# design.net
KiCad netlist of a schematic drawn in Altium Designer
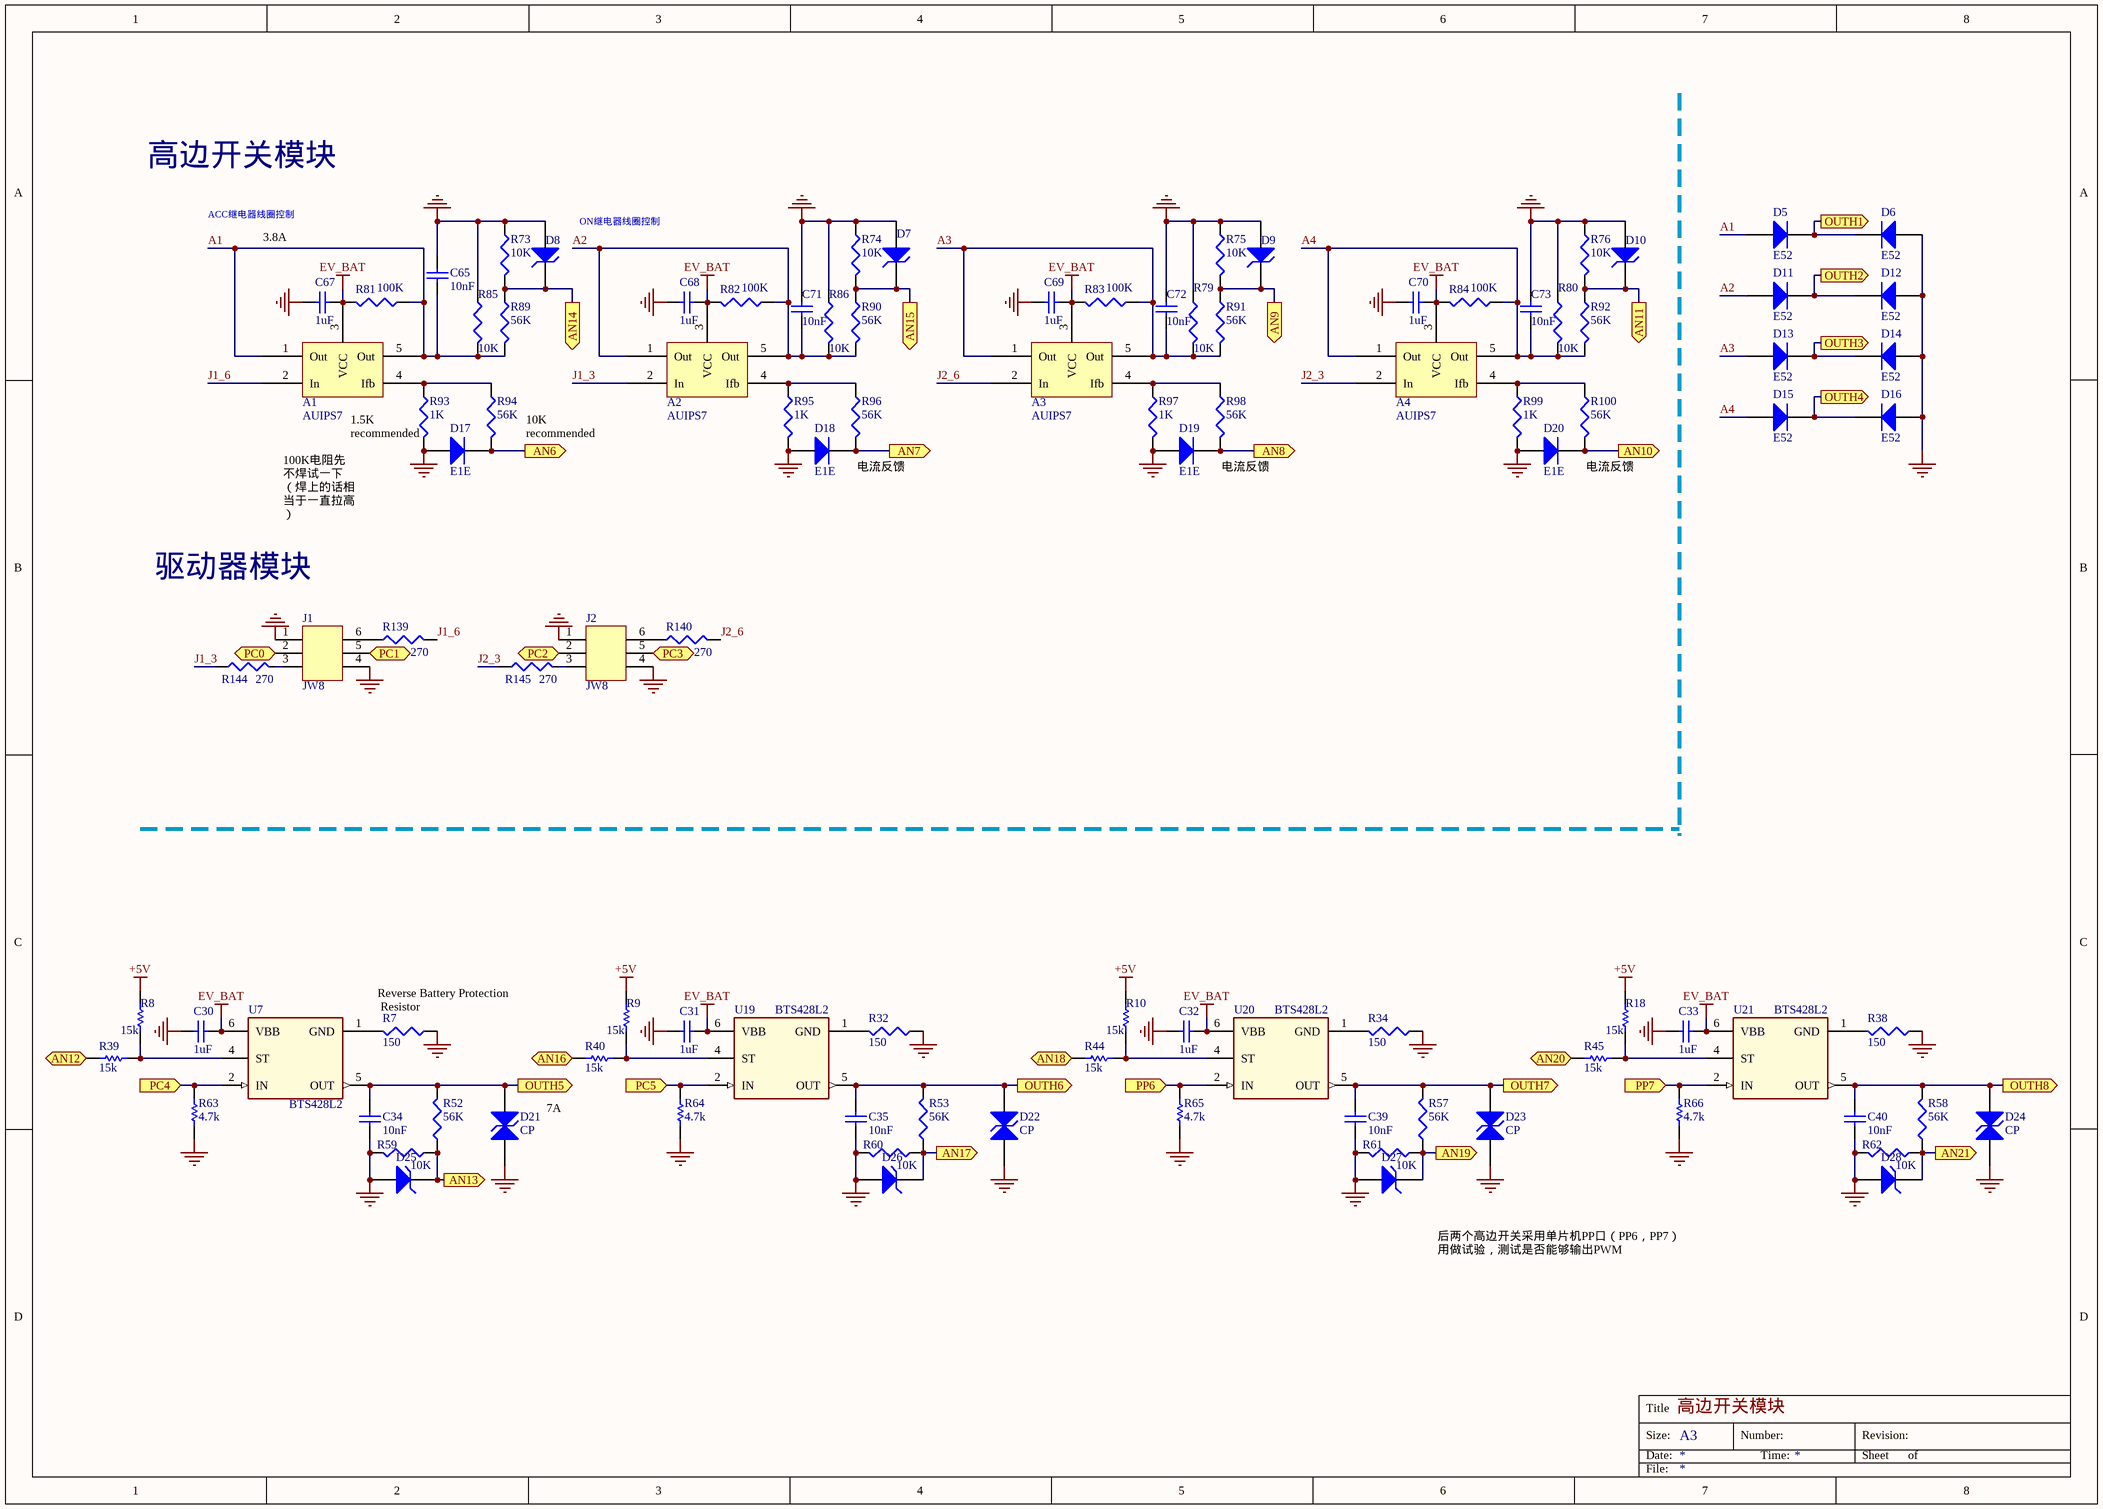
[diagram p0: 高边开关模块.SchDoc]

(export (version "E")
  (design (tool "Eeschema 10.0.6"))
  (components
    (comp (ref "A1") (value "AUIPS7") (footprint "AUIPS7") (libsource (lib "整车控制器") (part "AUIPS7")))
    (comp (ref "A2") (value "AUIPS7") (footprint "AUIPS7") (libsource (lib "整车控制器") (part "AUIPS7")))
    (comp (ref "A3") (value "AUIPS7") (footprint "AUIPS7") (libsource (lib "整车控制器") (part "AUIPS7")))
    (comp (ref "A4") (value "AUIPS7") (footprint "AUIPS7") (libsource (lib "整车控制器") (part "AUIPS7")))
    (comp (ref "C30")
      (value "1uF")
      (footprint "0603-L")
      (description "Capacitor")
      (fields (field (name "Comment") "Cap") (field (name "PUBLISHER") "Altium Limited"))
      (libsource (lib "Miscellaneous Devices") (part "Cap"))
    )
    (comp (ref "C31")
      (value "1uF")
      (footprint "0603-L")
      (description "Capacitor")
      (fields (field (name "Comment") "Cap") (field (name "PUBLISHER") "Altium Limited"))
      (libsource (lib "Miscellaneous Devices") (part "Cap"))
    )
    (comp (ref "C32")
      (value "1uF")
      (footprint "0603-L")
      (description "Capacitor")
      (fields (field (name "Comment") "Cap") (field (name "PUBLISHER") "Altium Limited"))
      (libsource (lib "Miscellaneous Devices") (part "Cap"))
    )
    (comp (ref "C33")
      (value "1uF")
      (footprint "0603-L")
      (description "Capacitor")
      (fields (field (name "Comment") "Cap") (field (name "PUBLISHER") "Altium Limited"))
      (libsource (lib "Miscellaneous Devices") (part "Cap"))
    )
    (comp (ref "C34")
      (value "10nF")
      (footprint "0603-L")
      (description "Capacitor")
      (fields (field (name "Comment") "Cap") (field (name "PUBLISHER") "Altium Limited"))
      (libsource (lib "Miscellaneous Devices") (part "Cap"))
    )
    (comp (ref "C35")
      (value "10nF")
      (footprint "0603-L")
      (description "Capacitor")
      (fields (field (name "Comment") "Cap") (field (name "PUBLISHER") "Altium Limited"))
      (libsource (lib "Miscellaneous Devices") (part "Cap"))
    )
    (comp (ref "C39")
      (value "10nF")
      (footprint "0603-L")
      (description "Capacitor")
      (fields (field (name "Comment") "Cap") (field (name "PUBLISHER") "Altium Limited"))
      (libsource (lib "Miscellaneous Devices") (part "Cap"))
    )
    (comp (ref "C40")
      (value "10nF")
      (footprint "0603-L")
      (description "Capacitor")
      (fields (field (name "Comment") "Cap") (field (name "PUBLISHER") "Altium Limited"))
      (libsource (lib "Miscellaneous Devices") (part "Cap"))
    )
    (comp (ref "C65")
      (value "10nF")
      (footprint "0603-L")
      (description "Capacitor")
      (fields (field (name "Comment") "Cap") (field (name "PUBLISHER") "Altium Limited"))
      (libsource (lib "Miscellaneous Devices") (part "Cap"))
    )
    (comp (ref "C67")
      (value "1uF")
      (footprint "0603-L")
      (description "Capacitor")
      (fields (field (name "Comment") "Cap") (field (name "PUBLISHER") "Altium Limited"))
      (libsource (lib "Miscellaneous Devices") (part "Cap"))
    )
    (comp (ref "C68")
      (value "1uF")
      (footprint "0603-L")
      (description "Capacitor")
      (fields (field (name "Comment") "Cap") (field (name "PUBLISHER") "Altium Limited"))
      (libsource (lib "Miscellaneous Devices") (part "Cap"))
    )
    (comp (ref "C69")
      (value "1uF")
      (footprint "0603-L")
      (description "Capacitor")
      (fields (field (name "Comment") "Cap") (field (name "PUBLISHER") "Altium Limited"))
      (libsource (lib "Miscellaneous Devices") (part "Cap"))
    )
    (comp (ref "C70")
      (value "1uF")
      (footprint "0603-L")
      (description "Capacitor")
      (fields (field (name "Comment") "Cap") (field (name "PUBLISHER") "Altium Limited"))
      (libsource (lib "Miscellaneous Devices") (part "Cap"))
    )
    (comp (ref "C71")
      (value "10nF")
      (footprint "0603-L")
      (description "Capacitor")
      (fields (field (name "Comment") "Cap") (field (name "PUBLISHER") "Altium Limited"))
      (libsource (lib "Miscellaneous Devices") (part "Cap"))
    )
    (comp (ref "C72")
      (value "10nF")
      (footprint "0603-L")
      (description "Capacitor")
      (fields (field (name "Comment") "Cap") (field (name "PUBLISHER") "Altium Limited"))
      (libsource (lib "Miscellaneous Devices") (part "Cap"))
    )
    (comp (ref "C73")
      (value "10nF")
      (footprint "0603-L")
      (description "Capacitor")
      (fields (field (name "Comment") "Cap") (field (name "PUBLISHER") "Altium Limited"))
      (libsource (lib "Miscellaneous Devices") (part "Cap"))
    )
    (comp (ref "D5")
      (value "E52")
      (footprint "整车控制器:E52")
      (description "Default Diode")
      (fields (field (name "PUBLISHER") "Altium Limited"))
      (libsource (lib "Miscellaneous Devices") (part "Diode"))
    )
    (comp (ref "D6")
      (value "E52")
      (footprint "整车控制器:E52")
      (description "Default Diode")
      (fields (field (name "PUBLISHER") "Altium Limited"))
      (libsource (lib "Miscellaneous Devices") (part "Diode"))
    )
    (comp (ref "D7")
      (value "D Zener")
      (footprint "0805")
      (description "Zener Diode")
      (fields (field (name "PUBLISHER") "Altium Limited"))
      (libsource (lib "Miscellaneous Devices") (part "D Zener"))
    )
    (comp (ref "D8")
      (value "D Zener")
      (footprint "0805")
      (description "Zener Diode")
      (fields (field (name "PUBLISHER") "Altium Limited"))
      (libsource (lib "Miscellaneous Devices") (part "D Zener"))
    )
    (comp (ref "D9")
      (value "D Zener")
      (footprint "0805")
      (description "Zener Diode")
      (fields (field (name "PUBLISHER") "Altium Limited"))
      (libsource (lib "Miscellaneous Devices") (part "D Zener"))
    )
    (comp (ref "D10")
      (value "D Zener")
      (footprint "0805")
      (description "Zener Diode")
      (fields (field (name "PUBLISHER") "Altium Limited"))
      (libsource (lib "Miscellaneous Devices") (part "D Zener"))
    )
    (comp (ref "D11")
      (value "E52")
      (footprint "整车控制器:E52")
      (description "Default Diode")
      (fields (field (name "PUBLISHER") "Altium Limited"))
      (libsource (lib "Miscellaneous Devices") (part "Diode"))
    )
    (comp (ref "D12")
      (value "E52")
      (footprint "整车控制器:E52")
      (description "Default Diode")
      (fields (field (name "PUBLISHER") "Altium Limited"))
      (libsource (lib "Miscellaneous Devices") (part "Diode"))
    )
    (comp (ref "D13")
      (value "E52")
      (footprint "整车控制器:E52")
      (description "Default Diode")
      (fields (field (name "PUBLISHER") "Altium Limited"))
      (libsource (lib "Miscellaneous Devices") (part "Diode"))
    )
    (comp (ref "D14")
      (value "E52")
      (footprint "整车控制器:E52")
      (description "Default Diode")
      (fields (field (name "PUBLISHER") "Altium Limited"))
      (libsource (lib "Miscellaneous Devices") (part "Diode"))
    )
    (comp (ref "D15")
      (value "E52")
      (footprint "整车控制器:E52")
      (description "Default Diode")
      (fields (field (name "PUBLISHER") "Altium Limited"))
      (libsource (lib "Miscellaneous Devices") (part "Diode"))
    )
    (comp (ref "D16")
      (value "E52")
      (footprint "整车控制器:E52")
      (description "Default Diode")
      (fields (field (name "PUBLISHER") "Altium Limited"))
      (libsource (lib "Miscellaneous Devices") (part "Diode"))
    )
    (comp (ref "D17")
      (value "E1E")
      (footprint "E1E")
      (description "Default Diode")
      (fields (field (name "PUBLISHER") "Altium Limited"))
      (libsource (lib "Miscellaneous Devices") (part "Diode"))
    )
    (comp (ref "D18")
      (value "E1E")
      (footprint "E1E")
      (description "Default Diode")
      (fields (field (name "PUBLISHER") "Altium Limited"))
      (libsource (lib "Miscellaneous Devices") (part "Diode"))
    )
    (comp (ref "D19")
      (value "E1E")
      (footprint "E1E")
      (description "Default Diode")
      (fields (field (name "PUBLISHER") "Altium Limited"))
      (libsource (lib "Miscellaneous Devices") (part "Diode"))
    )
    (comp (ref "D20")
      (value "E1E")
      (footprint "E1E")
      (description "Default Diode")
      (fields (field (name "PUBLISHER") "Altium Limited"))
      (libsource (lib "Miscellaneous Devices") (part "Diode"))
    )
    (comp (ref "D21") (value "CP") (footprint "E52") (libsource (lib "整车控制器") (part "CP")))
    (comp (ref "D22") (value "CP") (footprint "E52") (libsource (lib "整车控制器") (part "CP")))
    (comp (ref "D23") (value "CP") (footprint "E52") (libsource (lib "整车控制器") (part "CP")))
    (comp (ref "D24") (value "CP") (footprint "E52") (libsource (lib "整车控制器") (part "CP")))
    (comp (ref "D25")
      (value "D Zener")
      (footprint "0805")
      (description "Zener Diode")
      (fields (field (name "PUBLISHER") "Altium Limited"))
      (libsource (lib "Miscellaneous Devices") (part "D Zener"))
    )
    (comp (ref "D26")
      (value "D Zener")
      (footprint "0805")
      (description "Zener Diode")
      (fields (field (name "PUBLISHER") "Altium Limited"))
      (libsource (lib "Miscellaneous Devices") (part "D Zener"))
    )
    (comp (ref "D27")
      (value "D Zener")
      (footprint "0805")
      (description "Zener Diode")
      (fields (field (name "PUBLISHER") "Altium Limited"))
      (libsource (lib "Miscellaneous Devices") (part "D Zener"))
    )
    (comp (ref "D28")
      (value "D Zener")
      (footprint "0805")
      (description "Zener Diode")
      (fields (field (name "PUBLISHER") "Altium Limited"))
      (libsource (lib "Miscellaneous Devices") (part "D Zener"))
    )
    (comp (ref "J1")
      (value "JW8")
      (footprint "JW8")
      (description "inductive load driver")
      (libsource (lib "整车控制器") (part "JW8"))
    )
    (comp (ref "J2")
      (value "JW8")
      (footprint "JW8")
      (description "inductive load driver")
      (libsource (lib "整车控制器") (part "JW8"))
    )
    (comp (ref "R7")
      (value "150")
      (footprint "RES1206")
      (description "Resistor")
      (fields (field (name "Comment") "Res3") (field (name "PUBLISHER") "Altium Limited"))
      (libsource (lib "Miscellaneous Devices") (part "Res3"))
    )
    (comp (ref "R8")
      (value "15k")
      (footprint "0603-Resistor")
      (description "RES, 10k ohm, 0.1%, 0.1W, 0603")
      (fields
        (field (name "MANUFACTURER") "YAGEO")
        (field (name "PARTNUMBER") "RT0603BRD0710KL")
        (field (name "PUBLISHER") "YAGEO")
      )
      (libsource (lib "Resistor") (part "RT0603BRD0710KL"))
    )
    (comp (ref "R9")
      (value "15k")
      (footprint "0603-Resistor")
      (description "RES, 10k ohm, 0.1%, 0.1W, 0603")
      (fields
        (field (name "MANUFACTURER") "YAGEO")
        (field (name "PARTNUMBER") "RT0603BRD0710KL")
        (field (name "PUBLISHER") "YAGEO")
      )
      (libsource (lib "Resistor") (part "RT0603BRD0710KL"))
    )
    (comp (ref "R10")
      (value "15k")
      (footprint "0603-Resistor")
      (description "RES, 10k ohm, 0.1%, 0.1W, 0603")
      (fields
        (field (name "MANUFACTURER") "YAGEO")
        (field (name "PARTNUMBER") "RT0603BRD0710KL")
        (field (name "PUBLISHER") "YAGEO")
      )
      (libsource (lib "Resistor") (part "RT0603BRD0710KL"))
    )
    (comp (ref "R18")
      (value "15k")
      (footprint "0603-Resistor")
      (description "RES, 10k ohm, 0.1%, 0.1W, 0603")
      (fields
        (field (name "MANUFACTURER") "YAGEO")
        (field (name "PARTNUMBER") "RT0603BRD0710KL")
        (field (name "PUBLISHER") "YAGEO")
      )
      (libsource (lib "Resistor") (part "RT0603BRD0710KL"))
    )
    (comp (ref "R32")
      (value "150")
      (footprint "RES1206")
      (description "Resistor")
      (fields (field (name "Comment") "Res3") (field (name "PUBLISHER") "Altium Limited"))
      (libsource (lib "Miscellaneous Devices") (part "Res3"))
    )
    (comp (ref "R34")
      (value "150")
      (footprint "RES1206")
      (description "Resistor")
      (fields (field (name "Comment") "Res3") (field (name "PUBLISHER") "Altium Limited"))
      (libsource (lib "Miscellaneous Devices") (part "Res3"))
    )
    (comp (ref "R38")
      (value "150")
      (footprint "RES1206")
      (description "Resistor")
      (fields (field (name "Comment") "Res3") (field (name "PUBLISHER") "Altium Limited"))
      (libsource (lib "Miscellaneous Devices") (part "Res3"))
    )
    (comp (ref "R39")
      (value "15k")
      (footprint "0603-Resistor")
      (description "RES, 10k ohm, 0.1%, 0.1W, 0603")
      (fields
        (field (name "MANUFACTURER") "YAGEO")
        (field (name "PARTNUMBER") "RT0603BRD0710KL")
        (field (name "PUBLISHER") "YAGEO")
      )
      (libsource (lib "Resistor") (part "RT0603BRD0710KL"))
    )
    (comp (ref "R40")
      (value "15k")
      (footprint "0603-Resistor")
      (description "RES, 10k ohm, 0.1%, 0.1W, 0603")
      (fields
        (field (name "MANUFACTURER") "YAGEO")
        (field (name "PARTNUMBER") "RT0603BRD0710KL")
        (field (name "PUBLISHER") "YAGEO")
      )
      (libsource (lib "Resistor") (part "RT0603BRD0710KL"))
    )
    (comp (ref "R44")
      (value "15k")
      (footprint "0603-Resistor")
      (description "RES, 10k ohm, 0.1%, 0.1W, 0603")
      (fields
        (field (name "MANUFACTURER") "YAGEO")
        (field (name "PARTNUMBER") "RT0603BRD0710KL")
        (field (name "PUBLISHER") "YAGEO")
      )
      (libsource (lib "Resistor") (part "RT0603BRD0710KL"))
    )
    (comp (ref "R45")
      (value "15k")
      (footprint "0603-Resistor")
      (description "RES, 10k ohm, 0.1%, 0.1W, 0603")
      (fields
        (field (name "MANUFACTURER") "YAGEO")
        (field (name "PARTNUMBER") "RT0603BRD0710KL")
        (field (name "PUBLISHER") "YAGEO")
      )
      (libsource (lib "Resistor") (part "RT0603BRD0710KL"))
    )
    (comp (ref "R52")
      (value "56K")
      (footprint "0603-L")
      (description "Resistor")
      (fields (field (name "Comment") "Res3") (field (name "PUBLISHER") "Altium Limited"))
      (libsource (lib "Miscellaneous Devices") (part "Res3"))
    )
    (comp (ref "R53")
      (value "56K")
      (footprint "0603-L")
      (description "Resistor")
      (fields (field (name "Comment") "Res3") (field (name "PUBLISHER") "Altium Limited"))
      (libsource (lib "Miscellaneous Devices") (part "Res3"))
    )
    (comp (ref "R57")
      (value "56K")
      (footprint "0603-L")
      (description "Resistor")
      (fields (field (name "Comment") "Res3") (field (name "PUBLISHER") "Altium Limited"))
      (libsource (lib "Miscellaneous Devices") (part "Res3"))
    )
    (comp (ref "R58")
      (value "56K")
      (footprint "0603-L")
      (description "Resistor")
      (fields (field (name "Comment") "Res3") (field (name "PUBLISHER") "Altium Limited"))
      (libsource (lib "Miscellaneous Devices") (part "Res3"))
    )
    (comp (ref "R59")
      (value "10K")
      (footprint "0603-L")
      (description "Resistor")
      (fields (field (name "Comment") "Res3") (field (name "PUBLISHER") "Altium Limited"))
      (libsource (lib "Miscellaneous Devices") (part "Res3"))
    )
    (comp (ref "R60")
      (value "10K")
      (footprint "0603-L")
      (description "Resistor")
      (fields (field (name "Comment") "Res3") (field (name "PUBLISHER") "Altium Limited"))
      (libsource (lib "Miscellaneous Devices") (part "Res3"))
    )
    (comp (ref "R61")
      (value "10K")
      (footprint "0603-L")
      (description "Resistor")
      (fields (field (name "Comment") "Res3") (field (name "PUBLISHER") "Altium Limited"))
      (libsource (lib "Miscellaneous Devices") (part "Res3"))
    )
    (comp (ref "R62")
      (value "10K")
      (footprint "0603-L")
      (description "Resistor")
      (fields (field (name "Comment") "Res3") (field (name "PUBLISHER") "Altium Limited"))
      (libsource (lib "Miscellaneous Devices") (part "Res3"))
    )
    (comp (ref "R63")
      (value "4.7k")
      (footprint "0603-Resistor")
      (description "RES, 4.7k ohm, 1%, 0.1W, 0603")
      (fields
        (field (name "MANUFACTURER") "YAGEO")
        (field (name "PARTNUMBER") "RC0603FR-074K7L")
        (field (name "PUBLISHER") "YAGEO")
      )
      (libsource (lib "Resistor") (part "RC0603FR-074K7L"))
    )
    (comp (ref "R64")
      (value "4.7k")
      (footprint "0603-Resistor")
      (description "RES, 4.7k ohm, 1%, 0.1W, 0603")
      (fields
        (field (name "MANUFACTURER") "YAGEO")
        (field (name "PARTNUMBER") "RC0603FR-074K7L")
        (field (name "PUBLISHER") "YAGEO")
      )
      (libsource (lib "Resistor") (part "RC0603FR-074K7L"))
    )
    (comp (ref "R65")
      (value "4.7k")
      (footprint "0603-Resistor")
      (description "RES, 4.7k ohm, 1%, 0.1W, 0603")
      (fields
        (field (name "MANUFACTURER") "YAGEO")
        (field (name "PARTNUMBER") "RC0603FR-074K7L")
        (field (name "PUBLISHER") "YAGEO")
      )
      (libsource (lib "Resistor") (part "RC0603FR-074K7L"))
    )
    (comp (ref "R66")
      (value "4.7k")
      (footprint "0603-Resistor")
      (description "RES, 4.7k ohm, 1%, 0.1W, 0603")
      (fields
        (field (name "MANUFACTURER") "YAGEO")
        (field (name "PARTNUMBER") "RC0603FR-074K7L")
        (field (name "PUBLISHER") "YAGEO")
      )
      (libsource (lib "Resistor") (part "RC0603FR-074K7L"))
    )
    (comp (ref "R73")
      (value "10K")
      (footprint "0603-L")
      (description "Resistor")
      (fields (field (name "Comment") "Res3") (field (name "PUBLISHER") "Altium Limited"))
      (libsource (lib "Miscellaneous Devices") (part "Res3"))
    )
    (comp (ref "R74")
      (value "10K")
      (footprint "0603-L")
      (description "Resistor")
      (fields (field (name "Comment") "Res3") (field (name "PUBLISHER") "Altium Limited"))
      (libsource (lib "Miscellaneous Devices") (part "Res3"))
    )
    (comp (ref "R75")
      (value "10K")
      (footprint "0603-L")
      (description "Resistor")
      (fields (field (name "Comment") "Res3") (field (name "PUBLISHER") "Altium Limited"))
      (libsource (lib "Miscellaneous Devices") (part "Res3"))
    )
    (comp (ref "R76")
      (value "10K")
      (footprint "0603-L")
      (description "Resistor")
      (fields (field (name "Comment") "Res3") (field (name "PUBLISHER") "Altium Limited"))
      (libsource (lib "Miscellaneous Devices") (part "Res3"))
    )
    (comp (ref "R79")
      (value "10K")
      (footprint "0603-L")
      (description "Resistor")
      (fields (field (name "Comment") "Res3") (field (name "PUBLISHER") "Altium Limited"))
      (libsource (lib "Miscellaneous Devices") (part "Res3"))
    )
    (comp (ref "R80")
      (value "10K")
      (footprint "0603-L")
      (description "Resistor")
      (fields (field (name "Comment") "Res3") (field (name "PUBLISHER") "Altium Limited"))
      (libsource (lib "Miscellaneous Devices") (part "Res3"))
    )
    (comp (ref "R81")
      (value "100K")
      (footprint "0603-L")
      (description "Resistor")
      (fields (field (name "Comment") "Res3") (field (name "PUBLISHER") "Altium Limited"))
      (libsource (lib "Miscellaneous Devices") (part "Res3"))
    )
    (comp (ref "R82")
      (value "100K")
      (footprint "0603-L")
      (description "Resistor")
      (fields (field (name "Comment") "Res3") (field (name "PUBLISHER") "Altium Limited"))
      (libsource (lib "Miscellaneous Devices") (part "Res3"))
    )
    (comp (ref "R83")
      (value "100K")
      (footprint "0603-L")
      (description "Resistor")
      (fields (field (name "Comment") "Res3") (field (name "PUBLISHER") "Altium Limited"))
      (libsource (lib "Miscellaneous Devices") (part "Res3"))
    )
    (comp (ref "R84")
      (value "100K")
      (footprint "0603-L")
      (description "Resistor")
      (fields (field (name "Comment") "Res3") (field (name "PUBLISHER") "Altium Limited"))
      (libsource (lib "Miscellaneous Devices") (part "Res3"))
    )
    (comp (ref "R85")
      (value "10K")
      (footprint "0603-L")
      (description "Resistor")
      (fields (field (name "Comment") "Res3") (field (name "PUBLISHER") "Altium Limited"))
      (libsource (lib "Miscellaneous Devices") (part "Res3"))
    )
    (comp (ref "R86")
      (value "10K")
      (footprint "0603-L")
      (description "Resistor")
      (fields (field (name "Comment") "Res3") (field (name "PUBLISHER") "Altium Limited"))
      (libsource (lib "Miscellaneous Devices") (part "Res3"))
    )
    (comp (ref "R89")
      (value "56K")
      (footprint "0603-L")
      (description "Resistor")
      (fields (field (name "Comment") "Res3") (field (name "PUBLISHER") "Altium Limited"))
      (libsource (lib "Miscellaneous Devices") (part "Res3"))
    )
    (comp (ref "R90")
      (value "56K")
      (footprint "0603-L")
      (description "Resistor")
      (fields (field (name "Comment") "Res3") (field (name "PUBLISHER") "Altium Limited"))
      (libsource (lib "Miscellaneous Devices") (part "Res3"))
    )
    (comp (ref "R91")
      (value "56K")
      (footprint "0603-L")
      (description "Resistor")
      (fields (field (name "Comment") "Res3") (field (name "PUBLISHER") "Altium Limited"))
      (libsource (lib "Miscellaneous Devices") (part "Res3"))
    )
    (comp (ref "R92")
      (value "56K")
      (footprint "0603-L")
      (description "Resistor")
      (fields (field (name "Comment") "Res3") (field (name "PUBLISHER") "Altium Limited"))
      (libsource (lib "Miscellaneous Devices") (part "Res3"))
    )
    (comp (ref "R93")
      (value "1K")
      (footprint "RES1206")
      (description "Resistor")
      (fields (field (name "Comment") "Res3") (field (name "PUBLISHER") "Altium Limited"))
      (libsource (lib "Miscellaneous Devices") (part "Res3"))
    )
    (comp (ref "R94")
      (value "56K")
      (footprint "0603-L")
      (description "Resistor")
      (fields (field (name "Comment") "Res3") (field (name "PUBLISHER") "Altium Limited"))
      (libsource (lib "Miscellaneous Devices") (part "Res3"))
    )
    (comp (ref "R95")
      (value "1K")
      (footprint "RES1206")
      (description "Resistor")
      (fields (field (name "Comment") "Res3") (field (name "PUBLISHER") "Altium Limited"))
      (libsource (lib "Miscellaneous Devices") (part "Res3"))
    )
    (comp (ref "R96")
      (value "56K")
      (footprint "0603-L")
      (description "Resistor")
      (fields (field (name "Comment") "Res3") (field (name "PUBLISHER") "Altium Limited"))
      (libsource (lib "Miscellaneous Devices") (part "Res3"))
    )
    (comp (ref "R97")
      (value "1K")
      (footprint "RES1206")
      (description "Resistor")
      (fields (field (name "Comment") "Res3") (field (name "PUBLISHER") "Altium Limited"))
      (libsource (lib "Miscellaneous Devices") (part "Res3"))
    )
    (comp (ref "R98")
      (value "56K")
      (footprint "0603-L")
      (description "Resistor")
      (fields (field (name "Comment") "Res3") (field (name "PUBLISHER") "Altium Limited"))
      (libsource (lib "Miscellaneous Devices") (part "Res3"))
    )
    (comp (ref "R99")
      (value "1K")
      (footprint "RES1206")
      (description "Resistor")
      (fields (field (name "Comment") "Res3") (field (name "PUBLISHER") "Altium Limited"))
      (libsource (lib "Miscellaneous Devices") (part "Res3"))
    )
    (comp (ref "R100")
      (value "56K")
      (footprint "0603-L")
      (description "Resistor")
      (fields (field (name "Comment") "Res3") (field (name "PUBLISHER") "Altium Limited"))
      (libsource (lib "Miscellaneous Devices") (part "Res3"))
    )
    (comp (ref "R139")
      (value "270")
      (footprint "RES0805")
      (description "Resistor")
      (fields (field (name "Comment") "Res3") (field (name "PUBLISHER") "Altium Limited"))
      (libsource (lib "Miscellaneous Devices") (part "Res3"))
    )
    (comp (ref "R140")
      (value "270")
      (footprint "RES0805")
      (description "Resistor")
      (fields (field (name "Comment") "Res3") (field (name "PUBLISHER") "Altium Limited"))
      (libsource (lib "Miscellaneous Devices") (part "Res3"))
    )
    (comp (ref "R144")
      (value "270")
      (footprint "RES0805")
      (description "Resistor")
      (fields (field (name "Comment") "Res3") (field (name "PUBLISHER") "Altium Limited"))
      (libsource (lib "Miscellaneous Devices") (part "Res3"))
    )
    (comp (ref "R145")
      (value "270")
      (footprint "RES0805")
      (description "Resistor")
      (fields (field (name "Comment") "Res3") (field (name "PUBLISHER") "Altium Limited"))
      (libsource (lib "Miscellaneous Devices") (part "Res3"))
    )
    (comp (ref "U7")
      (value "BTS428L2")
      (footprint "TO114P998X235-6_5N-V")
      (description "Smart High-Side Power Switch, One Channel, 60mOhm, Status Feedback")
      (fields (field (name "MANUFACTURER") "Infineon Technologies"))
      (libsource (lib "BTS428L2") (part "BTS428L2"))
    )
    (comp (ref "U19")
      (value "BTS428L2")
      (footprint "TO114P998X235-6_5N-V")
      (description "Smart High-Side Power Switch, One Channel, 60mOhm, Status Feedback")
      (fields (field (name "MANUFACTURER") "Infineon Technologies"))
      (libsource (lib "BTS428L2") (part "BTS428L2"))
    )
    (comp (ref "U20")
      (value "BTS428L2")
      (footprint "TO114P998X235-6_5N-V")
      (description "Smart High-Side Power Switch, One Channel, 60mOhm, Status Feedback")
      (fields (field (name "MANUFACTURER") "Infineon Technologies"))
      (libsource (lib "BTS428L2") (part "BTS428L2"))
    )
    (comp (ref "U21")
      (value "BTS428L2")
      (footprint "TO114P998X235-6_5N-V")
      (description "Smart High-Side Power Switch, One Channel, 60mOhm, Status Feedback")
      (fields (field (name "MANUFACTURER") "Infineon Technologies"))
      (libsource (lib "BTS428L2") (part "BTS428L2"))
    )
  )
  (nets
    (net (code "1") (name "+5V") (class "Default")
      (node (ref "R10") (pin "2") (pinfunction "2_2") (pintype "passive"))
      (node (ref "R18") (pin "2") (pinfunction "2_2") (pintype "passive"))
      (node (ref "R8") (pin "2") (pinfunction "2_2") (pintype "passive"))
      (node (ref "R9") (pin "2") (pinfunction "2_2") (pintype "passive"))
    )
    (net (code "2") (name "/A1") (class "Default")
      (node (ref "A1") (pin "1") (pinfunction "Out_1") (pintype "passive"))
      (node (ref "A1") (pin "5") (pinfunction "Out_5") (pintype "passive"))
      (node (ref "C65") (pin "2") (pinfunction "2_2") (pintype "passive"))
      (node (ref "D5") (pin "1") (pinfunction "A_1") (pintype "passive"))
      (node (ref "R81") (pin "2") (pinfunction "2_2") (pintype "passive"))
      (node (ref "R85") (pin "1") (pinfunction "1_1") (pintype "passive"))
      (node (ref "R89") (pin "1") (pinfunction "1_1") (pintype "passive"))
    )
    (net (code "3") (name "/A2") (class "Default")
      (node (ref "A2") (pin "1") (pinfunction "Out_1") (pintype "passive"))
      (node (ref "A2") (pin "5") (pinfunction "Out_5") (pintype "passive"))
      (node (ref "C71") (pin "2") (pinfunction "2_2") (pintype "passive"))
      (node (ref "D11") (pin "1") (pinfunction "A_1") (pintype "passive"))
      (node (ref "R82") (pin "2") (pinfunction "2_2") (pintype "passive"))
      (node (ref "R86") (pin "1") (pinfunction "1_1") (pintype "passive"))
      (node (ref "R90") (pin "1") (pinfunction "1_1") (pintype "passive"))
    )
    (net (code "4") (name "/A3") (class "Default")
      (node (ref "A3") (pin "1") (pinfunction "Out_1") (pintype "passive"))
      (node (ref "A3") (pin "5") (pinfunction "Out_5") (pintype "passive"))
      (node (ref "C72") (pin "2") (pinfunction "2_2") (pintype "passive"))
      (node (ref "D13") (pin "1") (pinfunction "A_1") (pintype "passive"))
      (node (ref "R79") (pin "1") (pinfunction "1_1") (pintype "passive"))
      (node (ref "R83") (pin "2") (pinfunction "2_2") (pintype "passive"))
      (node (ref "R91") (pin "1") (pinfunction "1_1") (pintype "passive"))
    )
    (net (code "5") (name "/A4") (class "Default")
      (node (ref "A4") (pin "1") (pinfunction "Out_1") (pintype "passive"))
      (node (ref "A4") (pin "5") (pinfunction "Out_5") (pintype "passive"))
      (node (ref "C73") (pin "2") (pinfunction "2_2") (pintype "passive"))
      (node (ref "D15") (pin "1") (pinfunction "A_1") (pintype "passive"))
      (node (ref "R80") (pin "1") (pinfunction "1_1") (pintype "passive"))
      (node (ref "R84") (pin "2") (pinfunction "2_2") (pintype "passive"))
      (node (ref "R92") (pin "1") (pinfunction "1_1") (pintype "passive"))
    )
    (net (code "6") (name "/AN6") (class "Default")
      (node (ref "D17") (pin "2") (pinfunction "K_2") (pintype "passive"))
      (node (ref "R94") (pin "1") (pinfunction "1_1") (pintype "passive"))
    )
    (net (code "7") (name "/AN7") (class "Default")
      (node (ref "D18") (pin "2") (pinfunction "K_2") (pintype "passive"))
      (node (ref "R96") (pin "1") (pinfunction "1_1") (pintype "passive"))
    )
    (net (code "8") (name "/AN8") (class "Default")
      (node (ref "D19") (pin "2") (pinfunction "K_2") (pintype "passive"))
      (node (ref "R98") (pin "1") (pinfunction "1_1") (pintype "passive"))
    )
    (net (code "9") (name "/AN9") (class "Default")
      (node (ref "D9") (pin "2") (pinfunction "K_2") (pintype "passive"))
      (node (ref "R75") (pin "1") (pinfunction "1_1") (pintype "passive"))
      (node (ref "R91") (pin "2") (pinfunction "2_2") (pintype "passive"))
    )
    (net (code "10") (name "/AN10") (class "Default")
      (node (ref "D20") (pin "2") (pinfunction "K_2") (pintype "passive"))
      (node (ref "R100") (pin "1") (pinfunction "1_1") (pintype "passive"))
    )
    (net (code "11") (name "/AN11") (class "Default")
      (node (ref "D10") (pin "2") (pinfunction "K_2") (pintype "passive"))
      (node (ref "R76") (pin "1") (pinfunction "1_1") (pintype "passive"))
      (node (ref "R92") (pin "2") (pinfunction "2_2") (pintype "passive"))
    )
    (net (code "12") (name "/AN12") (class "Default")
      (node (ref "R39") (pin "1") (pinfunction "1_1") (pintype "passive"))
    )
    (net (code "13") (name "/AN13") (class "Default")
      (node (ref "D25") (pin "2") (pinfunction "K_2") (pintype "passive"))
      (node (ref "R52") (pin "2") (pinfunction "2_2") (pintype "passive"))
      (node (ref "R59") (pin "2") (pinfunction "2_2") (pintype "passive"))
    )
    (net (code "14") (name "/AN14") (class "Default")
      (node (ref "D8") (pin "2") (pinfunction "K_2") (pintype "passive"))
      (node (ref "R73") (pin "1") (pinfunction "1_1") (pintype "passive"))
      (node (ref "R89") (pin "2") (pinfunction "2_2") (pintype "passive"))
    )
    (net (code "15") (name "/AN15") (class "Default")
      (node (ref "D7") (pin "2") (pinfunction "K_2") (pintype "passive"))
      (node (ref "R74") (pin "1") (pinfunction "1_1") (pintype "passive"))
      (node (ref "R90") (pin "2") (pinfunction "2_2") (pintype "passive"))
    )
    (net (code "16") (name "/AN16") (class "Default")
      (node (ref "R40") (pin "1") (pinfunction "1_1") (pintype "passive"))
    )
    (net (code "17") (name "/AN17") (class "Default")
      (node (ref "D26") (pin "2") (pinfunction "K_2") (pintype "passive"))
      (node (ref "R53") (pin "2") (pinfunction "2_2") (pintype "passive"))
      (node (ref "R60") (pin "2") (pinfunction "2_2") (pintype "passive"))
    )
    (net (code "18") (name "/AN18") (class "Default")
      (node (ref "R44") (pin "1") (pinfunction "1_1") (pintype "passive"))
    )
    (net (code "19") (name "/AN19") (class "Default")
      (node (ref "D27") (pin "2") (pinfunction "K_2") (pintype "passive"))
      (node (ref "R57") (pin "2") (pinfunction "2_2") (pintype "passive"))
      (node (ref "R61") (pin "2") (pinfunction "2_2") (pintype "passive"))
    )
    (net (code "20") (name "/AN20") (class "Default")
      (node (ref "R45") (pin "1") (pinfunction "1_1") (pintype "passive"))
    )
    (net (code "21") (name "/AN21") (class "Default")
      (node (ref "D28") (pin "2") (pinfunction "K_2") (pintype "passive"))
      (node (ref "R58") (pin "2") (pinfunction "2_2") (pintype "passive"))
      (node (ref "R62") (pin "2") (pinfunction "2_2") (pintype "passive"))
    )
    (net (code "22") (name "/J1_3") (class "Default")
      (node (ref "A2") (pin "2") (pinfunction "In_2") (pintype "passive"))
      (node (ref "R144") (pin "1") (pinfunction "1_1") (pintype "passive"))
    )
    (net (code "23") (name "/J1_6") (class "Default")
      (node (ref "A1") (pin "2") (pinfunction "In_2") (pintype "passive"))
      (node (ref "R139") (pin "1") (pinfunction "1_1") (pintype "passive"))
    )
    (net (code "24") (name "/J2_3") (class "Default")
      (node (ref "A4") (pin "2") (pinfunction "In_2") (pintype "passive"))
      (node (ref "R145") (pin "1") (pinfunction "1_1") (pintype "passive"))
    )
    (net (code "25") (name "/J2_6") (class "Default")
      (node (ref "A3") (pin "2") (pinfunction "In_2") (pintype "passive"))
      (node (ref "R140") (pin "1") (pinfunction "1_1") (pintype "passive"))
    )
    (net (code "26") (name "/OUTH1") (class "Default")
      (node (ref "D5") (pin "2") (pinfunction "K_2") (pintype "passive"))
      (node (ref "D6") (pin "2") (pinfunction "K_2") (pintype "passive"))
    )
    (net (code "27") (name "/OUTH2") (class "Default")
      (node (ref "D11") (pin "2") (pinfunction "K_2") (pintype "passive"))
      (node (ref "D12") (pin "2") (pinfunction "K_2") (pintype "passive"))
    )
    (net (code "28") (name "/OUTH3") (class "Default")
      (node (ref "D13") (pin "2") (pinfunction "K_2") (pintype "passive"))
      (node (ref "D14") (pin "2") (pinfunction "K_2") (pintype "passive"))
    )
    (net (code "29") (name "/OUTH4") (class "Default")
      (node (ref "D15") (pin "2") (pinfunction "K_2") (pintype "passive"))
      (node (ref "D16") (pin "2") (pinfunction "K_2") (pintype "passive"))
    )
    (net (code "30") (name "/OUTH5") (class "Default")
      (node (ref "C34") (pin "1") (pinfunction "1_1") (pintype "passive"))
      (node (ref "D21") (pin "1") (pinfunction "A1_1") (pintype "passive"))
      (node (ref "R52") (pin "1") (pinfunction "1_1") (pintype "passive"))
      (node (ref "U7") (pin "5") (pinfunction "OUT_5") (pintype "output"))
    )
    (net (code "31") (name "/OUTH6") (class "Default")
      (node (ref "C35") (pin "1") (pinfunction "1_1") (pintype "passive"))
      (node (ref "D22") (pin "1") (pinfunction "A1_1") (pintype "passive"))
      (node (ref "R53") (pin "1") (pinfunction "1_1") (pintype "passive"))
      (node (ref "U19") (pin "5") (pinfunction "OUT_5") (pintype "output"))
    )
    (net (code "32") (name "/OUTH7") (class "Default")
      (node (ref "C39") (pin "1") (pinfunction "1_1") (pintype "passive"))
      (node (ref "D23") (pin "1") (pinfunction "A1_1") (pintype "passive"))
      (node (ref "R57") (pin "1") (pinfunction "1_1") (pintype "passive"))
      (node (ref "U20") (pin "5") (pinfunction "OUT_5") (pintype "output"))
    )
    (net (code "33") (name "/OUTH8") (class "Default")
      (node (ref "C40") (pin "1") (pinfunction "1_1") (pintype "passive"))
      (node (ref "D24") (pin "1") (pinfunction "A1_1") (pintype "passive"))
      (node (ref "R58") (pin "1") (pinfunction "1_1") (pintype "passive"))
      (node (ref "U21") (pin "5") (pinfunction "OUT_5") (pintype "output"))
    )
    (net (code "34") (name "/PC0") (class "Default")
      (node (ref "J1") (pin "2") (pinfunction "2_2") (pintype "passive"))
    )
    (net (code "35") (name "/PC1") (class "Default")
      (node (ref "J1") (pin "5") (pinfunction "5_5") (pintype "passive"))
    )
    (net (code "36") (name "/PC2") (class "Default")
      (node (ref "J2") (pin "2") (pinfunction "2_2") (pintype "passive"))
    )
    (net (code "37") (name "/PC3") (class "Default")
      (node (ref "J2") (pin "5") (pinfunction "5_5") (pintype "passive"))
    )
    (net (code "38") (name "/PC4") (class "Default")
      (node (ref "R63") (pin "2") (pinfunction "2_2") (pintype "passive"))
      (node (ref "U7") (pin "2") (pinfunction "IN_2") (pintype "input"))
    )
    (net (code "39") (name "/PC5") (class "Default")
      (node (ref "R64") (pin "2") (pinfunction "2_2") (pintype "passive"))
      (node (ref "U19") (pin "2") (pinfunction "IN_2") (pintype "input"))
    )
    (net (code "40") (name "/PP6") (class "Default")
      (node (ref "R65") (pin "2") (pinfunction "2_2") (pintype "passive"))
      (node (ref "U20") (pin "2") (pinfunction "IN_2") (pintype "input"))
    )
    (net (code "41") (name "/PP7") (class "Default")
      (node (ref "R66") (pin "2") (pinfunction "2_2") (pintype "passive"))
      (node (ref "U21") (pin "2") (pinfunction "IN_2") (pintype "input"))
    )
    (net (code "42") (name "EV_BAT") (class "Default")
      (node (ref "A1") (pin "3") (pinfunction "VCC_3") (pintype "passive"))
      (node (ref "A2") (pin "3") (pinfunction "VCC_3") (pintype "passive"))
      (node (ref "A3") (pin "3") (pinfunction "VCC_3") (pintype "passive"))
      (node (ref "A4") (pin "3") (pinfunction "VCC_3") (pintype "passive"))
      (node (ref "C30") (pin "1") (pinfunction "1_1") (pintype "passive"))
      (node (ref "C31") (pin "1") (pinfunction "1_1") (pintype "passive"))
      (node (ref "C32") (pin "1") (pinfunction "1_1") (pintype "passive"))
      (node (ref "C33") (pin "1") (pinfunction "1_1") (pintype "passive"))
      (node (ref "C67") (pin "1") (pinfunction "1_1") (pintype "passive"))
      (node (ref "C68") (pin "1") (pinfunction "1_1") (pintype "passive"))
      (node (ref "C69") (pin "1") (pinfunction "1_1") (pintype "passive"))
      (node (ref "C70") (pin "1") (pinfunction "1_1") (pintype "passive"))
      (node (ref "R81") (pin "1") (pinfunction "1_1") (pintype "passive"))
      (node (ref "R82") (pin "1") (pinfunction "1_1") (pintype "passive"))
      (node (ref "R83") (pin "1") (pinfunction "1_1") (pintype "passive"))
      (node (ref "R84") (pin "1") (pinfunction "1_1") (pintype "passive"))
      (node (ref "U19") (pin "6") (pinfunction "VBB_6") (pintype "power_in"))
      (node (ref "U20") (pin "6") (pinfunction "VBB_6") (pintype "power_in"))
      (node (ref "U21") (pin "6") (pinfunction "VBB_6") (pintype "power_in"))
      (node (ref "U7") (pin "6") (pinfunction "VBB_6") (pintype "power_in"))
    )
    (net (code "43") (name "GND") (class "Default")
      (node (ref "C30") (pin "2") (pinfunction "2_2") (pintype "passive"))
      (node (ref "C31") (pin "2") (pinfunction "2_2") (pintype "passive"))
      (node (ref "C32") (pin "2") (pinfunction "2_2") (pintype "passive"))
      (node (ref "C33") (pin "2") (pinfunction "2_2") (pintype "passive"))
      (node (ref "C34") (pin "2") (pinfunction "2_2") (pintype "passive"))
      (node (ref "C35") (pin "2") (pinfunction "2_2") (pintype "passive"))
      (node (ref "C39") (pin "2") (pinfunction "2_2") (pintype "passive"))
      (node (ref "C40") (pin "2") (pinfunction "2_2") (pintype "passive"))
      (node (ref "C65") (pin "1") (pinfunction "1_1") (pintype "passive"))
      (node (ref "C67") (pin "2") (pinfunction "2_2") (pintype "passive"))
      (node (ref "C68") (pin "2") (pinfunction "2_2") (pintype "passive"))
      (node (ref "C69") (pin "2") (pinfunction "2_2") (pintype "passive"))
      (node (ref "C70") (pin "2") (pinfunction "2_2") (pintype "passive"))
      (node (ref "C71") (pin "1") (pinfunction "1_1") (pintype "passive"))
      (node (ref "C72") (pin "1") (pinfunction "1_1") (pintype "passive"))
      (node (ref "C73") (pin "1") (pinfunction "1_1") (pintype "passive"))
      (node (ref "D10") (pin "1") (pinfunction "A_1") (pintype "passive"))
      (node (ref "D12") (pin "1") (pinfunction "A_1") (pintype "passive"))
      (node (ref "D14") (pin "1") (pinfunction "A_1") (pintype "passive"))
      (node (ref "D16") (pin "1") (pinfunction "A_1") (pintype "passive"))
      (node (ref "D17") (pin "1") (pinfunction "A_1") (pintype "passive"))
      (node (ref "D18") (pin "1") (pinfunction "A_1") (pintype "passive"))
      (node (ref "D19") (pin "1") (pinfunction "A_1") (pintype "passive"))
      (node (ref "D20") (pin "1") (pinfunction "A_1") (pintype "passive"))
      (node (ref "D21") (pin "2") (pinfunction "A2_2") (pintype "passive"))
      (node (ref "D22") (pin "2") (pinfunction "A2_2") (pintype "passive"))
      (node (ref "D23") (pin "2") (pinfunction "A2_2") (pintype "passive"))
      (node (ref "D24") (pin "2") (pinfunction "A2_2") (pintype "passive"))
      (node (ref "D25") (pin "1") (pinfunction "A_1") (pintype "passive"))
      (node (ref "D26") (pin "1") (pinfunction "A_1") (pintype "passive"))
      (node (ref "D27") (pin "1") (pinfunction "A_1") (pintype "passive"))
      (node (ref "D28") (pin "1") (pinfunction "A_1") (pintype "passive"))
      (node (ref "D6") (pin "1") (pinfunction "A_1") (pintype "passive"))
      (node (ref "D7") (pin "1") (pinfunction "A_1") (pintype "passive"))
      (node (ref "D8") (pin "1") (pinfunction "A_1") (pintype "passive"))
      (node (ref "D9") (pin "1") (pinfunction "A_1") (pintype "passive"))
      (node (ref "J1") (pin "1") (pinfunction "1_1") (pintype "passive"))
      (node (ref "J1") (pin "4") (pinfunction "4_4") (pintype "passive"))
      (node (ref "J2") (pin "1") (pinfunction "1_1") (pintype "passive"))
      (node (ref "J2") (pin "4") (pinfunction "4_4") (pintype "passive"))
      (node (ref "R32") (pin "1") (pinfunction "1_1") (pintype "passive"))
      (node (ref "R34") (pin "1") (pinfunction "1_1") (pintype "passive"))
      (node (ref "R38") (pin "1") (pinfunction "1_1") (pintype "passive"))
      (node (ref "R59") (pin "1") (pinfunction "1_1") (pintype "passive"))
      (node (ref "R60") (pin "1") (pinfunction "1_1") (pintype "passive"))
      (node (ref "R61") (pin "1") (pinfunction "1_1") (pintype "passive"))
      (node (ref "R62") (pin "1") (pinfunction "1_1") (pintype "passive"))
      (node (ref "R63") (pin "1") (pinfunction "1_1") (pintype "passive"))
      (node (ref "R64") (pin "1") (pinfunction "1_1") (pintype "passive"))
      (node (ref "R65") (pin "1") (pinfunction "1_1") (pintype "passive"))
      (node (ref "R66") (pin "1") (pinfunction "1_1") (pintype "passive"))
      (node (ref "R7") (pin "1") (pinfunction "1_1") (pintype "passive"))
      (node (ref "R73") (pin "2") (pinfunction "2_2") (pintype "passive"))
      (node (ref "R74") (pin "2") (pinfunction "2_2") (pintype "passive"))
      (node (ref "R75") (pin "2") (pinfunction "2_2") (pintype "passive"))
      (node (ref "R76") (pin "2") (pinfunction "2_2") (pintype "passive"))
      (node (ref "R79") (pin "2") (pinfunction "2_2") (pintype "passive"))
      (node (ref "R80") (pin "2") (pinfunction "2_2") (pintype "passive"))
      (node (ref "R85") (pin "2") (pinfunction "2_2") (pintype "passive"))
      (node (ref "R86") (pin "2") (pinfunction "2_2") (pintype "passive"))
      (node (ref "R93") (pin "1") (pinfunction "1_1") (pintype "passive"))
      (node (ref "R95") (pin "1") (pinfunction "1_1") (pintype "passive"))
      (node (ref "R97") (pin "1") (pinfunction "1_1") (pintype "passive"))
      (node (ref "R99") (pin "1") (pinfunction "1_1") (pintype "passive"))
    )
    (net (code "44") (name "Net-(A1-Ifb)") (class "Default")
      (node (ref "A1") (pin "4") (pinfunction "Ifb_4") (pintype "passive"))
      (node (ref "R93") (pin "2") (pinfunction "2_2") (pintype "passive"))
      (node (ref "R94") (pin "2") (pinfunction "2_2") (pintype "passive"))
    )
    (net (code "45") (name "Net-(A2-Ifb)") (class "Default")
      (node (ref "A2") (pin "4") (pinfunction "Ifb_4") (pintype "passive"))
      (node (ref "R95") (pin "2") (pinfunction "2_2") (pintype "passive"))
      (node (ref "R96") (pin "2") (pinfunction "2_2") (pintype "passive"))
    )
    (net (code "46") (name "Net-(A3-Ifb)") (class "Default")
      (node (ref "A3") (pin "4") (pinfunction "Ifb_4") (pintype "passive"))
      (node (ref "R97") (pin "2") (pinfunction "2_2") (pintype "passive"))
      (node (ref "R98") (pin "2") (pinfunction "2_2") (pintype "passive"))
    )
    (net (code "47") (name "Net-(A4-Ifb)") (class "Default")
      (node (ref "A4") (pin "4") (pinfunction "Ifb_4") (pintype "passive"))
      (node (ref "R100") (pin "2") (pinfunction "2_2") (pintype "passive"))
      (node (ref "R99") (pin "2") (pinfunction "2_2") (pintype "passive"))
    )
    (net (code "48") (name "Net-(J1-Pad3)") (class "Default")
      (node (ref "J1") (pin "3") (pinfunction "3_3") (pintype "passive"))
      (node (ref "R144") (pin "2") (pinfunction "2_2") (pintype "passive"))
    )
    (net (code "49") (name "Net-(J1-Pad6)") (class "Default")
      (node (ref "J1") (pin "6") (pinfunction "6_6") (pintype "passive"))
      (node (ref "R139") (pin "2") (pinfunction "2_2") (pintype "passive"))
    )
    (net (code "50") (name "Net-(J2-Pad3)") (class "Default")
      (node (ref "J2") (pin "3") (pinfunction "3_3") (pintype "passive"))
      (node (ref "R145") (pin "2") (pinfunction "2_2") (pintype "passive"))
    )
    (net (code "51") (name "Net-(J2-Pad6)") (class "Default")
      (node (ref "J2") (pin "6") (pinfunction "6_6") (pintype "passive"))
      (node (ref "R140") (pin "2") (pinfunction "2_2") (pintype "passive"))
    )
    (net (code "52") (name "Net-(U7-GND)") (class "Default")
      (node (ref "R7") (pin "2") (pinfunction "2_2") (pintype "passive"))
      (node (ref "U7") (pin "1") (pinfunction "GND_1") (pintype "power_in"))
    )
    (net (code "53") (name "Net-(U7-ST)") (class "Default")
      (node (ref "R39") (pin "2") (pinfunction "2_2") (pintype "passive"))
      (node (ref "R8") (pin "1") (pinfunction "1_1") (pintype "passive"))
      (node (ref "U7") (pin "4") (pinfunction "ST_4") (pintype "open_collector"))
    )
    (net (code "54") (name "Net-(U19-GND)") (class "Default")
      (node (ref "R32") (pin "2") (pinfunction "2_2") (pintype "passive"))
      (node (ref "U19") (pin "1") (pinfunction "GND_1") (pintype "power_in"))
    )
    (net (code "55") (name "Net-(U19-ST)") (class "Default")
      (node (ref "R40") (pin "2") (pinfunction "2_2") (pintype "passive"))
      (node (ref "R9") (pin "1") (pinfunction "1_1") (pintype "passive"))
      (node (ref "U19") (pin "4") (pinfunction "ST_4") (pintype "open_collector"))
    )
    (net (code "56") (name "Net-(U20-GND)") (class "Default")
      (node (ref "R34") (pin "2") (pinfunction "2_2") (pintype "passive"))
      (node (ref "U20") (pin "1") (pinfunction "GND_1") (pintype "power_in"))
    )
    (net (code "57") (name "Net-(U20-ST)") (class "Default")
      (node (ref "R10") (pin "1") (pinfunction "1_1") (pintype "passive"))
      (node (ref "R44") (pin "2") (pinfunction "2_2") (pintype "passive"))
      (node (ref "U20") (pin "4") (pinfunction "ST_4") (pintype "open_collector"))
    )
    (net (code "58") (name "Net-(U21-GND)") (class "Default")
      (node (ref "R38") (pin "2") (pinfunction "2_2") (pintype "passive"))
      (node (ref "U21") (pin "1") (pinfunction "GND_1") (pintype "power_in"))
    )
    (net (code "59") (name "Net-(U21-ST)") (class "Default")
      (node (ref "R18") (pin "1") (pinfunction "1_1") (pintype "passive"))
      (node (ref "R45") (pin "2") (pinfunction "2_2") (pintype "passive"))
      (node (ref "U21") (pin "4") (pinfunction "ST_4") (pintype "open_collector"))
    )
  )
)
